# breadboard_rev05.net
KiCad netlist of a schematic drawn in EAGLE
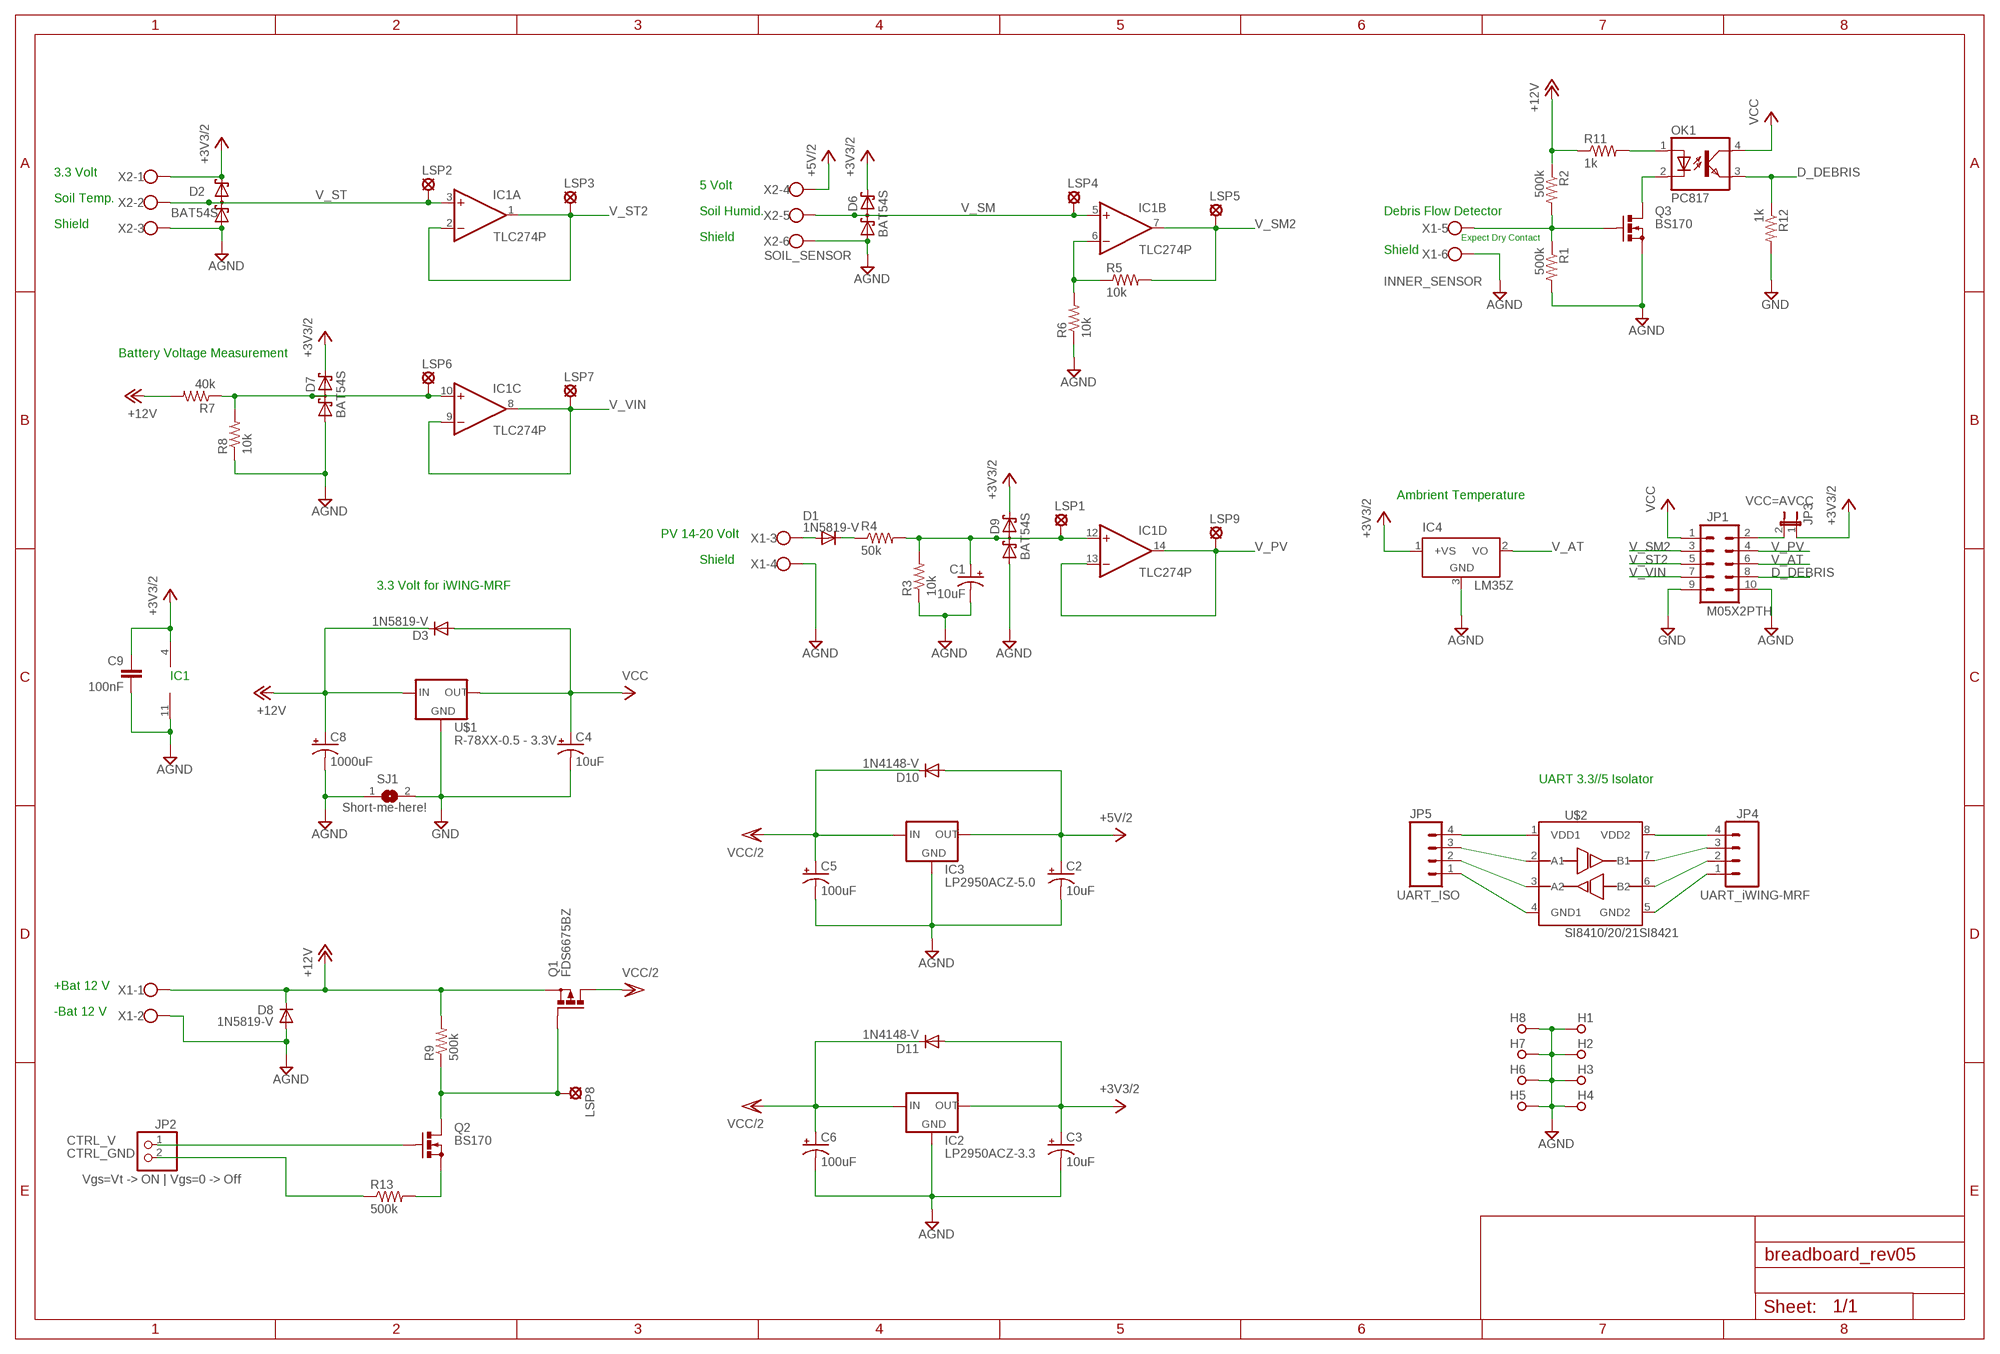
[diagram p0: schematic, sheet 1]

(export (version "E")
  (design (tool "Eeschema 10.0.6"))
  (components
    (comp (ref "C1")
      (value "10uF")
      (footprint "eagle-import:RCL_E2,5-7")
      (libsource (lib "eagle-import") (part "RCL_CPOL-USE2.5-7"))
    )
    (comp (ref "C2")
      (value "10uF")
      (footprint "eagle-import:RCL_E2,5-7")
      (libsource (lib "eagle-import") (part "RCL_CPOL-USE2.5-7"))
    )
    (comp (ref "C3")
      (value "10uF")
      (footprint "eagle-import:RCL_E2,5-7")
      (libsource (lib "eagle-import") (part "RCL_CPOL-USE2.5-7"))
    )
    (comp (ref "C4")
      (value "10uF")
      (footprint "eagle-import:RCL_E2,5-7")
      (libsource (lib "eagle-import") (part "RCL_CPOL-USE2.5-7"))
    )
    (comp (ref "C5")
      (value "100uF")
      (footprint "eagle-import:RCL_E2,5-7")
      (libsource (lib "eagle-import") (part "RCL_CPOL-USE2.5-7"))
    )
    (comp (ref "C6")
      (value "100uF")
      (footprint "eagle-import:RCL_E2,5-7")
      (libsource (lib "eagle-import") (part "RCL_CPOL-USE2.5-7"))
    )
    (comp (ref "C8")
      (value "1000uF")
      (footprint "eagle-import:RCL_E5-13")
      (libsource (lib "eagle-import") (part "RCL_CPOL-USE5-13"))
    )
    (comp (ref "C9")
      (value "100nF")
      (footprint "eagle-import:RCL_C050-025X075")
      (libsource (lib "eagle-import") (part "RCL_C-EU050-025X075"))
    )
    (comp (ref "D1")
      (value "1N5819-V")
      (footprint "eagle-import:DO41-150V")
      (libsource (lib "eagle-import") (part "1N5819-V"))
    )
    (comp (ref "D2")
      (value "BAT54S")
      (footprint "eagle-import:SOT23")
      (libsource (lib "eagle-import") (part "BAT54S"))
    )
    (comp (ref "D3")
      (value "1N5819-V")
      (footprint "eagle-import:DO41-150V")
      (libsource (lib "eagle-import") (part "1N5819-V"))
    )
    (comp (ref "D6")
      (value "BAT54S")
      (footprint "eagle-import:SOT23")
      (libsource (lib "eagle-import") (part "BAT54S"))
    )
    (comp (ref "D7")
      (value "BAT54S")
      (footprint "eagle-import:SOT23")
      (libsource (lib "eagle-import") (part "BAT54S"))
    )
    (comp (ref "D8")
      (value "1N5819-V")
      (footprint "eagle-import:DO41-150V")
      (libsource (lib "eagle-import") (part "1N5819-V"))
    )
    (comp (ref "D9")
      (value "BAT54S")
      (footprint "eagle-import:SOT23")
      (libsource (lib "eagle-import") (part "BAT54S"))
    )
    (comp (ref "D10")
      (value "1N4148-V")
      (footprint "eagle-import:DO35-100V")
      (libsource (lib "eagle-import") (part "1N4148-V"))
    )
    (comp (ref "D11")
      (value "1N4148-V")
      (footprint "eagle-import:DO35-100V")
      (libsource (lib "eagle-import") (part "1N4148-V"))
    )
    (comp (ref "H1")
      (value "SPECIAL_DRILL_0.1560")
      (footprint "eagle-import:PAD_0.1560")
      (libsource (lib "eagle-import") (part "SPECIAL_DRILL_0.1560"))
    )
    (comp (ref "H2")
      (value "SPECIAL_DRILL_0.1560")
      (footprint "eagle-import:PAD_0.1560")
      (libsource (lib "eagle-import") (part "SPECIAL_DRILL_0.1560"))
    )
    (comp (ref "H3")
      (value "SPECIAL_DRILL_0.1560")
      (footprint "eagle-import:PAD_0.1560")
      (libsource (lib "eagle-import") (part "SPECIAL_DRILL_0.1560"))
    )
    (comp (ref "H4")
      (value "SPECIAL_DRILL_0.1560")
      (footprint "eagle-import:PAD_0.1560")
      (libsource (lib "eagle-import") (part "SPECIAL_DRILL_0.1560"))
    )
    (comp (ref "H5")
      (value "SPECIAL_DRILL_0.1560")
      (footprint "eagle-import:PAD_0.1560")
      (libsource (lib "eagle-import") (part "SPECIAL_DRILL_0.1560"))
    )
    (comp (ref "H6")
      (value "SPECIAL_DRILL_0.1560")
      (footprint "eagle-import:PAD_0.1560")
      (libsource (lib "eagle-import") (part "SPECIAL_DRILL_0.1560"))
    )
    (comp (ref "H7")
      (value "SPECIAL_DRILL_0.1560")
      (footprint "eagle-import:PAD_0.1560")
      (libsource (lib "eagle-import") (part "SPECIAL_DRILL_0.1560"))
    )
    (comp (ref "H8")
      (value "SPECIAL_DRILL_0.1560")
      (footprint "eagle-import:PAD_0.1560")
      (libsource (lib "eagle-import") (part "SPECIAL_DRILL_0.1560"))
    )
    (comp (ref "IC1")
      (value "TLC274P")
      (footprint "eagle-import:DIL14")
      (libsource (lib "eagle-import") (part "TLC274P"))
    )
    (comp (ref "IC2")
      (value "LP2950ACZ-3.3")
      (footprint "eagle-import:TO92")
      (libsource (lib "eagle-import") (part "LP2950?ACZ-3.3"))
    )
    (comp (ref "IC3")
      (value "LP2950ACZ-5.0")
      (footprint "eagle-import:TO92")
      (libsource (lib "eagle-import") (part "LP2950?ACZ-5.0"))
    )
    (comp (ref "IC4")
      (value "LM35Z")
      (footprint "eagle-import:TO92")
      (libsource (lib "eagle-import") (part "LM35?Z"))
    )
    (comp (ref "JP1")
      (value "M05X2PTH")
      (footprint "eagle-import:AVR_ICSP")
      (libsource (lib "eagle-import") (part "M05X2PTH"))
    )
    (comp (ref "JP2")
      (value "Vgs=Vt -> ON | Vgs=0 -> Off")
      (footprint "eagle-import:1X02")
      (libsource (lib "eagle-import") (part "PINHD-1X2"))
    )
    (comp (ref "JP3")
      (value "VCC=AVCC")
      (footprint "eagle-import:JUMPER_JP1")
      (libsource (lib "eagle-import") (part "JP1E"))
    )
    (comp (ref "JP4")
      (value "UART_iWING-MRF")
      (footprint "eagle-import:MOLEX-1X4")
      (libsource (lib "eagle-import") (part "M04POLAR"))
    )
    (comp (ref "JP5")
      (value "UART_ISO")
      (footprint "eagle-import:MOLEX-1X4")
      (libsource (lib "eagle-import") (part "M04POLAR"))
    )
    (comp (ref "LSP1")
      (value "LSP13")
      (footprint "eagle-import:LSP13")
      (libsource (lib "eagle-import") (part "LSP13"))
    )
    (comp (ref "LSP2")
      (value "LSP13")
      (footprint "eagle-import:LSP13")
      (libsource (lib "eagle-import") (part "LSP13"))
    )
    (comp (ref "LSP3")
      (value "LSP13")
      (footprint "eagle-import:LSP13")
      (libsource (lib "eagle-import") (part "LSP13"))
    )
    (comp (ref "LSP4")
      (value "LSP13")
      (footprint "eagle-import:LSP13")
      (libsource (lib "eagle-import") (part "LSP13"))
    )
    (comp (ref "LSP5")
      (value "LSP13")
      (footprint "eagle-import:LSP13")
      (libsource (lib "eagle-import") (part "LSP13"))
    )
    (comp (ref "LSP6")
      (value "LSP13")
      (footprint "eagle-import:LSP13")
      (libsource (lib "eagle-import") (part "LSP13"))
    )
    (comp (ref "LSP7")
      (value "LSP13")
      (footprint "eagle-import:LSP13")
      (libsource (lib "eagle-import") (part "LSP13"))
    )
    (comp (ref "LSP8")
      (value "LSP13")
      (footprint "eagle-import:LSP13")
      (libsource (lib "eagle-import") (part "LSP13"))
    )
    (comp (ref "LSP9")
      (value "LSP13")
      (footprint "eagle-import:LSP13")
      (libsource (lib "eagle-import") (part "LSP13"))
    )
    (comp (ref "OK1")
      (value "PC817")
      (footprint "eagle-import:DIL04")
      (fields (field (name "MPN") "PC817X4J000F"))
      (libsource (lib "eagle-import") (part "PC817"))
    )
    (comp (ref "Q1")
      (value "FDS6675BZ")
      (footprint "eagle-import:SO-08")
      (libsource (lib "eagle-import") (part "P-MOSFET-SO8"))
    )
    (comp (ref "Q2")
      (value "BS170")
      (footprint "eagle-import:SOT54E")
      (libsource (lib "eagle-import") (part "BS170"))
    )
    (comp (ref "Q3")
      (value "BS170")
      (footprint "eagle-import:SOT54E")
      (libsource (lib "eagle-import") (part "BS170"))
    )
    (comp (ref "R1")
      (value "500k")
      (footprint "eagle-import:RCL_0204_7")
      (libsource (lib "eagle-import") (part "RCL_R-US_0204/7"))
    )
    (comp (ref "R2")
      (value "500k")
      (footprint "eagle-import:RCL_0204_7")
      (libsource (lib "eagle-import") (part "RCL_R-US_0204/7"))
    )
    (comp (ref "R3")
      (value "10k")
      (footprint "eagle-import:RCL_0204_7")
      (libsource (lib "eagle-import") (part "RCL_R-US_0204/7"))
    )
    (comp (ref "R4")
      (value "50k")
      (footprint "eagle-import:RCL_0204_7")
      (libsource (lib "eagle-import") (part "RCL_R-US_0204/7"))
    )
    (comp (ref "R5")
      (value "10k")
      (footprint "eagle-import:RCL_0204_7")
      (libsource (lib "eagle-import") (part "RCL_R-US_0204/7"))
    )
    (comp (ref "R6")
      (value "10k")
      (footprint "eagle-import:RCL_0204_7")
      (libsource (lib "eagle-import") (part "RCL_R-US_0204/7"))
    )
    (comp (ref "R7")
      (value "40k")
      (footprint "eagle-import:RCL_0204_7")
      (libsource (lib "eagle-import") (part "RCL_R-US_0204/7"))
    )
    (comp (ref "R8")
      (value "10k")
      (footprint "eagle-import:RCL_0204_7")
      (libsource (lib "eagle-import") (part "RCL_R-US_0204/7"))
    )
    (comp (ref "R9")
      (value "500k")
      (footprint "eagle-import:RCL_0204_7")
      (libsource (lib "eagle-import") (part "RCL_R-US_0204/7"))
    )
    (comp (ref "R11")
      (value "1k")
      (footprint "eagle-import:RCL_0204_7")
      (libsource (lib "eagle-import") (part "RCL_R-US_0204/7"))
    )
    (comp (ref "R12")
      (value "1k")
      (footprint "eagle-import:RCL_0204_7")
      (libsource (lib "eagle-import") (part "RCL_R-US_0204/7"))
    )
    (comp (ref "R13")
      (value "500k")
      (footprint "eagle-import:RCL_0204_7")
      (libsource (lib "eagle-import") (part "RCL_R-US_0204/7"))
    )
    (comp (ref "SJ1")
      (value "Short-me-here!")
      (footprint "eagle-import:SJ")
      (libsource (lib "eagle-import") (part "SJ"))
    )
    (comp (ref "U$1")
      (value "R-78XX-0.5 - 3.3V")
      (footprint "eagle-import:SIP3")
      (libsource (lib "eagle-import") (part "R-78XX-0.5"))
    )
    (comp (ref "U$2")
      (value "SI8410/20/21SI8421")
      (footprint "eagle-import:SO-08")
      (libsource (lib "eagle-import") (part "SI8410/20/21SI8421"))
    )
    (comp (ref "X1")
      (value "INNER_SENSOR")
      (footprint "eagle-import:5EHDRC-6P")
      (libsource (lib "eagle-import") (part "5EHDRC-6P"))
    )
    (comp (ref "X2")
      (value "SOIL_SENSOR")
      (footprint "eagle-import:5EHDRC-6P")
      (libsource (lib "eagle-import") (part "5EHDRC-6P"))
    )
  )
  (nets
    (net (code "1") (name "+3V3{slash}2") (class "Default")
      (node (ref "C3") (pin "+") (pinfunction "+_+") (pintype "passive"))
      (node (ref "C9") (pin "1") (pinfunction "1_1") (pintype "passive"))
      (node (ref "D11") (pin "A") (pinfunction "A_A") (pintype "passive"))
      (node (ref "D2") (pin "2") (pinfunction "C2_2") (pintype "passive"))
      (node (ref "D6") (pin "2") (pinfunction "C2_2") (pintype "passive"))
      (node (ref "D7") (pin "2") (pinfunction "C2_2") (pintype "passive"))
      (node (ref "D9") (pin "2") (pinfunction "C2_2") (pintype "passive"))
      (node (ref "IC1") (pin "4") (pinfunction "V+_4") (pintype "power_in"))
      (node (ref "IC2") (pin "1") (pinfunction "OUT_1") (pintype "passive"))
      (node (ref "IC4") (pin "1") (pinfunction "+VS_1") (pintype "input"))
      (node (ref "JP3") (pin "1") (pinfunction "1_1") (pintype "passive"))
      (node (ref "X2") (pin "1") (pinfunction "KL_1") (pintype "passive"))
    )
    (net (code "2") (name "+5V{slash}2") (class "Default")
      (node (ref "C2") (pin "+") (pinfunction "+_+") (pintype "passive"))
      (node (ref "D10") (pin "A") (pinfunction "A_A") (pintype "passive"))
      (node (ref "IC3") (pin "1") (pinfunction "OUT_1") (pintype "passive"))
      (node (ref "X2") (pin "4") (pinfunction "KL_4") (pintype "passive"))
    )
    (net (code "3") (name "+12V") (class "Default")
      (node (ref "C8") (pin "+") (pinfunction "+_+") (pintype "passive"))
      (node (ref "D3") (pin "C") (pinfunction "C_C") (pintype "passive"))
      (node (ref "D8") (pin "C") (pinfunction "C_C") (pintype "passive"))
      (node (ref "Q1") (pin "1") (pinfunction "S_1") (pintype "passive"))
      (node (ref "Q1") (pin "2") (pinfunction "S_2") (pintype "passive"))
      (node (ref "Q1") (pin "3") (pinfunction "S_3") (pintype "passive"))
      (node (ref "R11") (pin "1") (pinfunction "1_1") (pintype "passive"))
      (node (ref "R2") (pin "1") (pinfunction "1_1") (pintype "passive"))
      (node (ref "R7") (pin "2") (pinfunction "2_2") (pintype "passive"))
      (node (ref "R9") (pin "2") (pinfunction "2_2") (pintype "passive"))
      (node (ref "U$1") (pin "1") (pinfunction "IN_1") (pintype "input"))
      (node (ref "X1") (pin "1") (pinfunction "KL_1") (pintype "passive"))
    )
    (net (code "4") (name "/CTRL_GND") (class "Default")
      (node (ref "JP2") (pin "2") (pinfunction "2_2") (pintype "passive"))
      (node (ref "R13") (pin "1") (pinfunction "1_1") (pintype "passive"))
    )
    (net (code "5") (name "/CTRL_V") (class "Default")
      (node (ref "JP2") (pin "1") (pinfunction "1_1") (pintype "passive"))
      (node (ref "Q2") (pin "G") (pinfunction "G_G") (pintype "passive"))
    )
    (net (code "6") (name "/D_DEBRIS") (class "Default")
      (node (ref "JP1") (pin "8") (pinfunction "8_8") (pintype "passive"))
      (node (ref "OK1") (pin "3") (pinfunction "EMIT_3") (pintype "passive"))
      (node (ref "R12") (pin "1") (pinfunction "1_1") (pintype "passive"))
    )
    (net (code "7") (name "/V_AT") (class "Default")
      (node (ref "IC4") (pin "2") (pinfunction "VO_2") (pintype "output"))
      (node (ref "JP1") (pin "6") (pinfunction "6_6") (pintype "passive"))
    )
    (net (code "8") (name "/V_PV") (class "Default")
      (node (ref "IC1") (pin "13") (pinfunction "-IN_13") (pintype "input"))
      (node (ref "IC1") (pin "14") (pinfunction "OUT_14") (pintype "output"))
      (node (ref "JP1") (pin "4") (pinfunction "4_4") (pintype "passive"))
      (node (ref "LSP9") (pin "MP") (pinfunction "MP_MP") (pintype "passive"))
    )
    (net (code "9") (name "/V_SM") (class "Default")
      (node (ref "D6") (pin "3") (pinfunction "C1A2_3") (pintype "passive"))
      (node (ref "IC1") (pin "5") (pinfunction "+IN_5") (pintype "input"))
      (node (ref "LSP4") (pin "MP") (pinfunction "MP_MP") (pintype "passive"))
      (node (ref "X2") (pin "5") (pinfunction "KL_5") (pintype "passive"))
    )
    (net (code "10") (name "/V_SM2") (class "Default")
      (node (ref "IC1") (pin "7") (pinfunction "OUT_7") (pintype "output"))
      (node (ref "JP1") (pin "3") (pinfunction "3_3") (pintype "passive"))
      (node (ref "LSP5") (pin "MP") (pinfunction "MP_MP") (pintype "passive"))
      (node (ref "R5") (pin "2") (pinfunction "2_2") (pintype "passive"))
    )
    (net (code "11") (name "/V_ST") (class "Default")
      (node (ref "D2") (pin "3") (pinfunction "C1A2_3") (pintype "passive"))
      (node (ref "IC1") (pin "3") (pinfunction "+IN_3") (pintype "input"))
      (node (ref "LSP2") (pin "MP") (pinfunction "MP_MP") (pintype "passive"))
      (node (ref "X2") (pin "2") (pinfunction "KL_2") (pintype "passive"))
    )
    (net (code "12") (name "/V_ST2") (class "Default")
      (node (ref "IC1") (pin "1") (pinfunction "OUT_1") (pintype "output"))
      (node (ref "IC1") (pin "2") (pinfunction "-IN_2") (pintype "input"))
      (node (ref "JP1") (pin "5") (pinfunction "5_5") (pintype "passive"))
      (node (ref "LSP3") (pin "MP") (pinfunction "MP_MP") (pintype "passive"))
    )
    (net (code "13") (name "/V_VIN") (class "Default")
      (node (ref "IC1") (pin "8") (pinfunction "OUT_8") (pintype "output"))
      (node (ref "IC1") (pin "9") (pinfunction "-IN_9") (pintype "input"))
      (node (ref "JP1") (pin "7") (pinfunction "7_7") (pintype "passive"))
      (node (ref "LSP7") (pin "MP") (pinfunction "MP_MP") (pintype "passive"))
    )
    (net (code "14") (name "AGND") (class "Default")
      (node (ref "C1") (pin "-") (pinfunction "-_-") (pintype "passive"))
      (node (ref "C2") (pin "-") (pinfunction "-_-") (pintype "passive"))
      (node (ref "C3") (pin "-") (pinfunction "-_-") (pintype "passive"))
      (node (ref "C5") (pin "-") (pinfunction "-_-") (pintype "passive"))
      (node (ref "C6") (pin "-") (pinfunction "-_-") (pintype "passive"))
      (node (ref "C8") (pin "-") (pinfunction "-_-") (pintype "passive"))
      (node (ref "C9") (pin "2") (pinfunction "2_2") (pintype "passive"))
      (node (ref "D2") (pin "1") (pinfunction "A1_1") (pintype "passive"))
      (node (ref "D6") (pin "1") (pinfunction "A1_1") (pintype "passive"))
      (node (ref "D7") (pin "1") (pinfunction "A1_1") (pintype "passive"))
      (node (ref "D8") (pin "A") (pinfunction "A_A") (pintype "passive"))
      (node (ref "D9") (pin "1") (pinfunction "A1_1") (pintype "passive"))
      (node (ref "H1") (pin "1") (pinfunction "1_1") (pintype "passive"))
      (node (ref "H2") (pin "1") (pinfunction "1_1") (pintype "passive"))
      (node (ref "H3") (pin "1") (pinfunction "1_1") (pintype "passive"))
      (node (ref "H4") (pin "1") (pinfunction "1_1") (pintype "passive"))
      (node (ref "H5") (pin "1") (pinfunction "1_1") (pintype "passive"))
      (node (ref "H6") (pin "1") (pinfunction "1_1") (pintype "passive"))
      (node (ref "H7") (pin "1") (pinfunction "1_1") (pintype "passive"))
      (node (ref "H8") (pin "1") (pinfunction "1_1") (pintype "passive"))
      (node (ref "IC1") (pin "11") (pinfunction "V-_11") (pintype "power_in"))
      (node (ref "IC2") (pin "2") (pinfunction "GND_2") (pintype "input"))
      (node (ref "IC3") (pin "2") (pinfunction "GND_2") (pintype "input"))
      (node (ref "IC4") (pin "3") (pinfunction "GND_3") (pintype "power_in"))
      (node (ref "JP1") (pin "10") (pinfunction "10_10") (pintype "passive"))
      (node (ref "Q3") (pin "S") (pinfunction "S_S") (pintype "passive"))
      (node (ref "R1") (pin "2") (pinfunction "2_2") (pintype "passive"))
      (node (ref "R3") (pin "1") (pinfunction "1_1") (pintype "passive"))
      (node (ref "R6") (pin "1") (pinfunction "1_1") (pintype "passive"))
      (node (ref "R8") (pin "1") (pinfunction "1_1") (pintype "passive"))
      (node (ref "SJ1") (pin "1") (pinfunction "1_1") (pintype "passive"))
      (node (ref "X1") (pin "2") (pinfunction "KL_2") (pintype "passive"))
      (node (ref "X1") (pin "4") (pinfunction "KL_4") (pintype "passive"))
      (node (ref "X1") (pin "6") (pinfunction "KL_6") (pintype "passive"))
      (node (ref "X2") (pin "3") (pinfunction "KL_3") (pintype "passive"))
      (node (ref "X2") (pin "6") (pinfunction "KL_6") (pintype "passive"))
    )
    (net (code "15") (name "GND") (class "Default")
      (node (ref "C4") (pin "-") (pinfunction "-_-") (pintype "passive"))
      (node (ref "JP1") (pin "9") (pinfunction "9_9") (pintype "passive"))
      (node (ref "R12") (pin "2") (pinfunction "2_2") (pintype "passive"))
      (node (ref "SJ1") (pin "2") (pinfunction "2_2") (pintype "passive"))
      (node (ref "U$1") (pin "2") (pinfunction "GND_2") (pintype "input"))
    )
    (net (code "16") (name "Net-(D1-PadC)") (class "Default")
      (node (ref "D1") (pin "C") (pinfunction "C_C") (pintype "passive"))
      (node (ref "R4") (pin "1") (pinfunction "1_1") (pintype "passive"))
    )
    (net (code "17") (name "Net-(D7-C1A2)") (class "Default")
      (node (ref "D7") (pin "3") (pinfunction "C1A2_3") (pintype "passive"))
      (node (ref "IC1") (pin "10") (pinfunction "+IN_10") (pintype "input"))
      (node (ref "LSP6") (pin "MP") (pinfunction "MP_MP") (pintype "passive"))
      (node (ref "R7") (pin "1") (pinfunction "1_1") (pintype "passive"))
      (node (ref "R8") (pin "2") (pinfunction "2_2") (pintype "passive"))
    )
    (net (code "18") (name "Net-(D9-C1A2)") (class "Default")
      (node (ref "C1") (pin "+") (pinfunction "+_+") (pintype "passive"))
      (node (ref "D9") (pin "3") (pinfunction "C1A2_3") (pintype "passive"))
      (node (ref "IC1") (pin "12") (pinfunction "+IN_12") (pintype "input"))
      (node (ref "LSP1") (pin "MP") (pinfunction "MP_MP") (pintype "passive"))
      (node (ref "R3") (pin "2") (pinfunction "2_2") (pintype "passive"))
      (node (ref "R4") (pin "2") (pinfunction "2_2") (pintype "passive"))
    )
    (net (code "19") (name "Net-(IC1B--IN)") (class "Default")
      (node (ref "IC1") (pin "6") (pinfunction "-IN_6") (pintype "input"))
      (node (ref "R5") (pin "1") (pinfunction "1_1") (pintype "passive"))
      (node (ref "R6") (pin "2") (pinfunction "2_2") (pintype "passive"))
    )
    (net (code "20") (name "Net-(JP1-Pad2)") (class "Default")
      (node (ref "JP1") (pin "2") (pinfunction "2_2") (pintype "passive"))
      (node (ref "JP3") (pin "2") (pinfunction "2_2") (pintype "passive"))
    )
    (net (code "21") (name "Net-(OK1-A)") (class "Default")
      (node (ref "OK1") (pin "1") (pinfunction "A_1") (pintype "passive"))
      (node (ref "R11") (pin "2") (pinfunction "2_2") (pintype "passive"))
    )
    (net (code "22") (name "Net-(OK1-C)") (class "Default")
      (node (ref "OK1") (pin "2") (pinfunction "C_2") (pintype "passive"))
      (node (ref "Q3") (pin "D") (pinfunction "D_D") (pintype "passive"))
    )
    (net (code "23") (name "Net-(Q1-G)") (class "Default")
      (node (ref "LSP8") (pin "MP") (pinfunction "MP_MP") (pintype "passive"))
      (node (ref "Q1") (pin "4") (pinfunction "G_4") (pintype "passive"))
      (node (ref "Q2") (pin "D") (pinfunction "D_D") (pintype "passive"))
      (node (ref "R9") (pin "1") (pinfunction "1_1") (pintype "passive"))
    )
    (net (code "24") (name "Net-(Q2-PadS)") (class "Default")
      (node (ref "Q2") (pin "S") (pinfunction "S_S") (pintype "passive"))
      (node (ref "R13") (pin "2") (pinfunction "2_2") (pintype "passive"))
    )
    (net (code "25") (name "Net-(U$2-A1)") (class "Default")
      (node (ref "JP5") (pin "3") (pinfunction "3_3") (pintype "passive"))
      (node (ref "U$2") (pin "2") (pinfunction "A1_2") (pintype "input"))
    )
    (net (code "26") (name "Net-(U$2-A2)") (class "Default")
      (node (ref "JP5") (pin "2") (pinfunction "2_2") (pintype "passive"))
      (node (ref "U$2") (pin "3") (pinfunction "A2_3") (pintype "output"))
    )
    (net (code "27") (name "Net-(U$2-B1)") (class "Default")
      (node (ref "JP4") (pin "3") (pinfunction "3_3") (pintype "passive"))
      (node (ref "U$2") (pin "7") (pinfunction "B1_7") (pintype "output"))
    )
    (net (code "28") (name "Net-(U$2-B2)") (class "Default")
      (node (ref "JP4") (pin "2") (pinfunction "2_2") (pintype "passive"))
      (node (ref "U$2") (pin "6") (pinfunction "B2_6") (pintype "input"))
    )
    (net (code "29") (name "Net-(U$2-GND1)") (class "Default")
      (node (ref "JP5") (pin "1") (pinfunction "1_1") (pintype "passive"))
      (node (ref "U$2") (pin "4") (pinfunction "GND1_4") (pintype "power_in"))
    )
    (net (code "30") (name "Net-(U$2-GND2)") (class "Default")
      (node (ref "JP4") (pin "1") (pinfunction "1_1") (pintype "passive"))
      (node (ref "U$2") (pin "5") (pinfunction "GND2_5") (pintype "power_in"))
    )
    (net (code "31") (name "Net-(U$2-VDD1)") (class "Default")
      (node (ref "JP5") (pin "4") (pinfunction "4_4") (pintype "passive"))
      (node (ref "U$2") (pin "1") (pinfunction "VDD1_1") (pintype "power_in"))
    )
    (net (code "32") (name "Net-(U$2-VDD2)") (class "Default")
      (node (ref "JP4") (pin "4") (pinfunction "4_4") (pintype "passive"))
      (node (ref "U$2") (pin "8") (pinfunction "VDD2_8") (pintype "power_in"))
    )
    (net (code "33") (name "Net-(X1C-KL)") (class "Default")
      (node (ref "D1") (pin "A") (pinfunction "A_A") (pintype "passive"))
      (node (ref "X1") (pin "3") (pinfunction "KL_3") (pintype "passive"))
    )
    (net (code "34") (name "Net-(X1E-KL)") (class "Default")
      (node (ref "Q3") (pin "G") (pinfunction "G_G") (pintype "passive"))
      (node (ref "R1") (pin "1") (pinfunction "1_1") (pintype "passive"))
      (node (ref "R2") (pin "2") (pinfunction "2_2") (pintype "passive"))
      (node (ref "X1") (pin "5") (pinfunction "KL_5") (pintype "passive"))
    )
    (net (code "35") (name "VCC") (class "Default")
      (node (ref "C4") (pin "+") (pinfunction "+_+") (pintype "passive"))
      (node (ref "D3") (pin "A") (pinfunction "A_A") (pintype "passive"))
      (node (ref "JP1") (pin "1") (pinfunction "1_1") (pintype "passive"))
      (node (ref "OK1") (pin "4") (pinfunction "COL_4") (pintype "passive"))
      (node (ref "U$1") (pin "3") (pinfunction "OUT_3") (pintype "passive"))
    )
    (net (code "36") (name "VCC{slash}2") (class "Default")
      (node (ref "C5") (pin "+") (pinfunction "+_+") (pintype "passive"))
      (node (ref "C6") (pin "+") (pinfunction "+_+") (pintype "passive"))
      (node (ref "D10") (pin "C") (pinfunction "C_C") (pintype "passive"))
      (node (ref "D11") (pin "C") (pinfunction "C_C") (pintype "passive"))
      (node (ref "IC2") (pin "3") (pinfunction "IN_3") (pintype "input"))
      (node (ref "IC3") (pin "3") (pinfunction "IN_3") (pintype "input"))
      (node (ref "Q1") (pin "5") (pinfunction "D_5") (pintype "passive"))
      (node (ref "Q1") (pin "6") (pinfunction "D_6") (pintype "passive"))
      (node (ref "Q1") (pin "7") (pinfunction "D_7") (pintype "passive"))
      (node (ref "Q1") (pin "8") (pinfunction "D_8") (pintype "passive"))
    )
  )
)
